# Macropad-Advanced.net
KiCad netlist of a schematic drawn in EasyEDA Pro
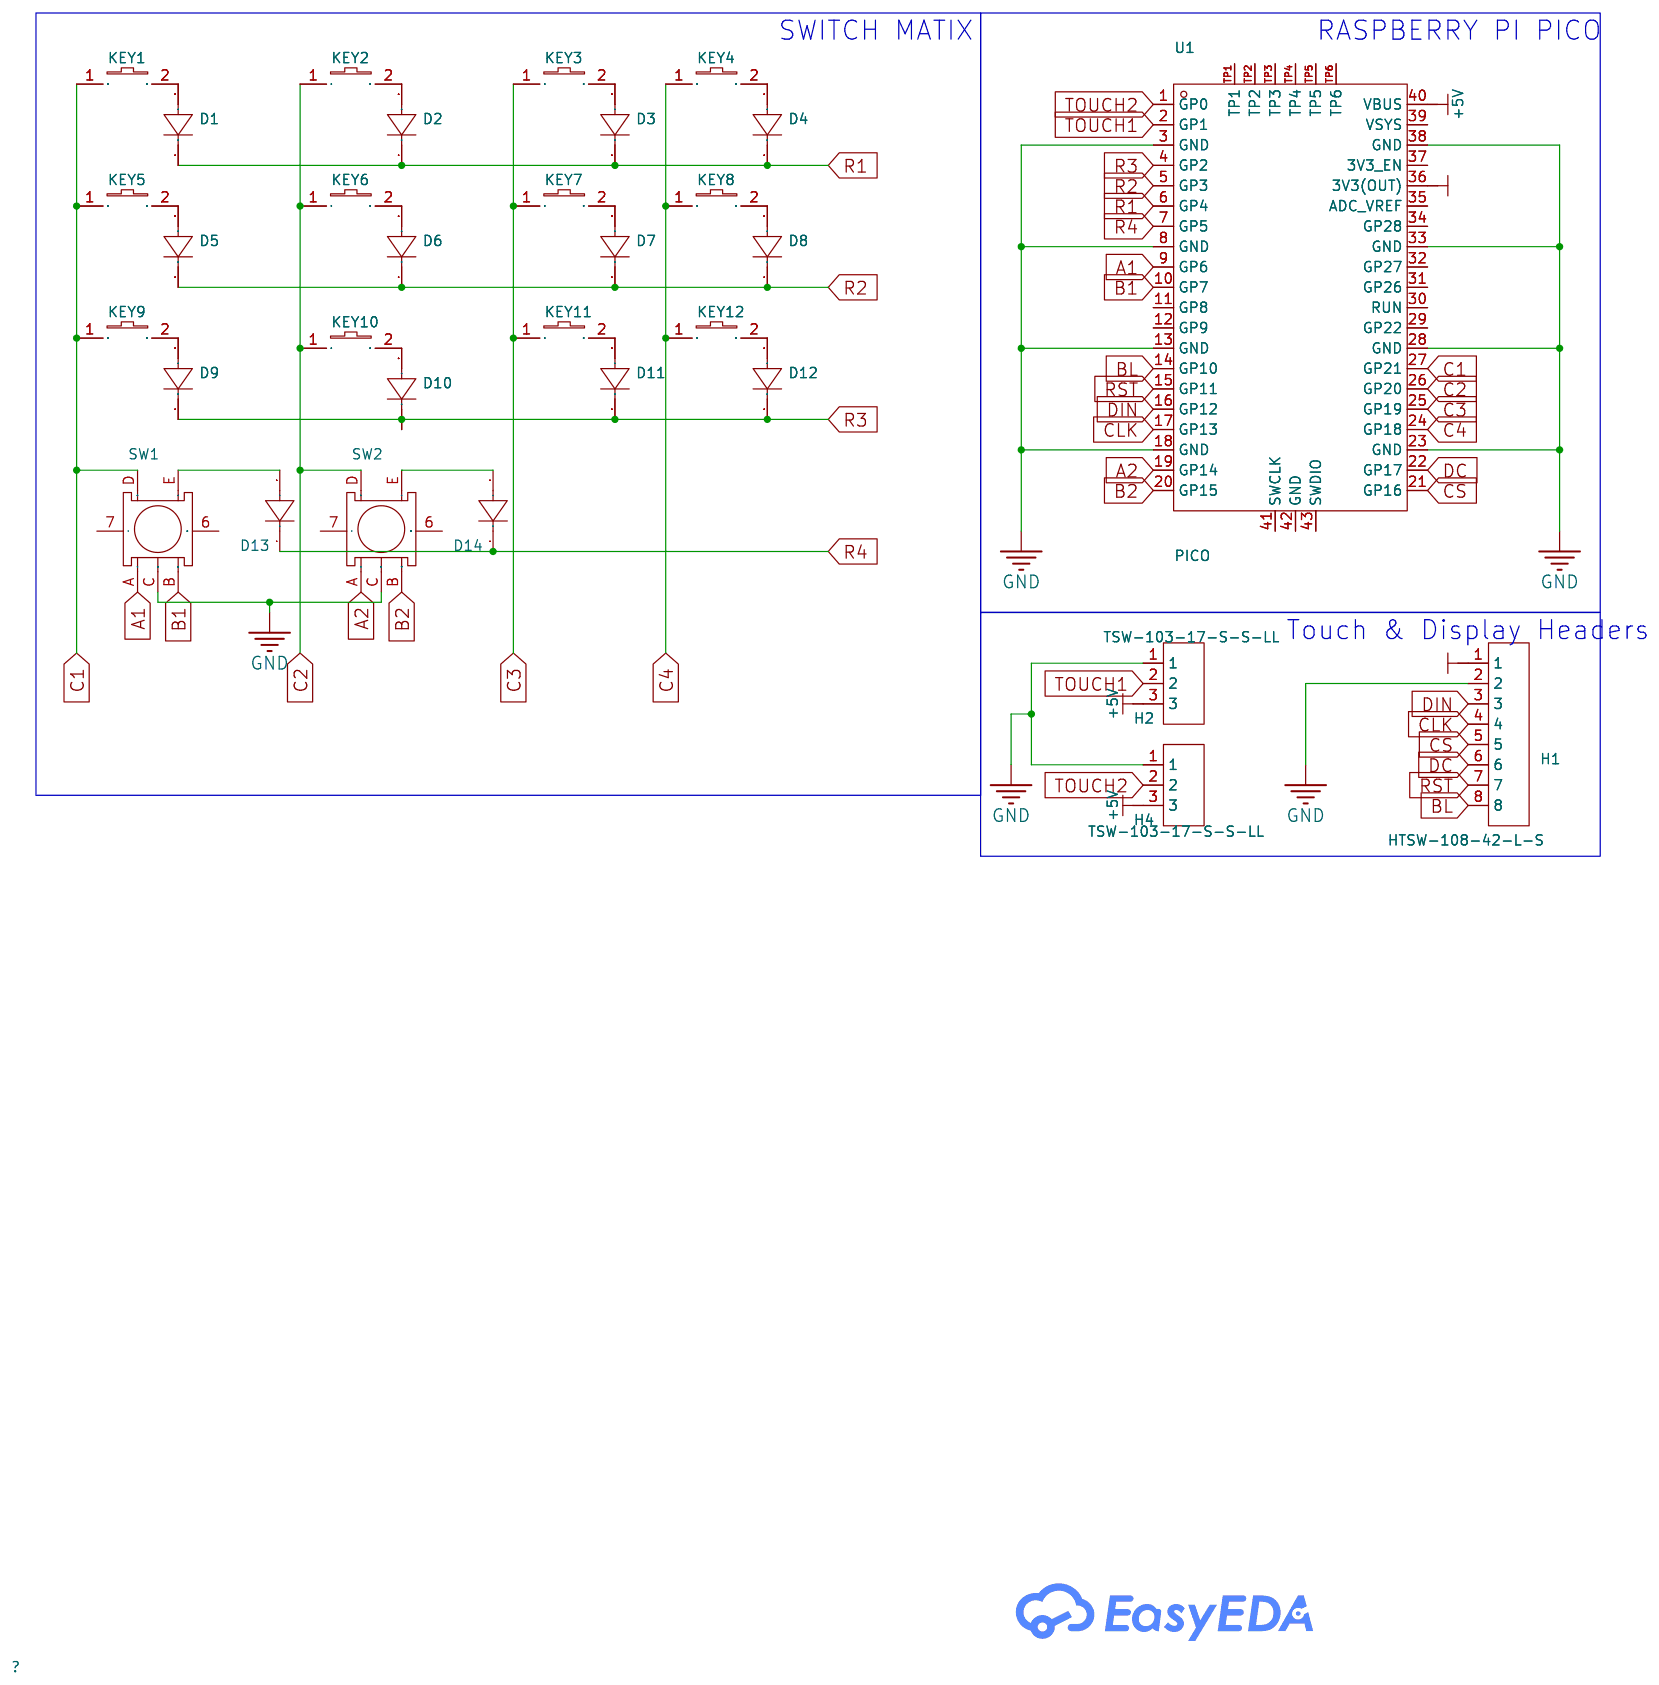
[diagram p0: schematic sheet]

(export (version "E")
  (design (tool "Eeschema 10.0.6"))
  (components
    (comp (ref "D1")
      (value "~")
      (footprint "easyedapro:DO-41_BD2.4-L4.7-P8.70-D0.9-RD")
      (fields (field (name "Manufacturer Part") "1N4148") (field (name "Manufacturer") "ST(先科)"))
      (libsource (lib "easyedapro") (part "D_1N4007"))
    )
    (comp (ref "D2")
      (value "~")
      (footprint "easyedapro:DO-41_BD2.4-L4.7-P8.70-D0.9-RD")
      (fields (field (name "Manufacturer Part") "1N4148") (field (name "Manufacturer") "ST(先科)"))
      (libsource (lib "easyedapro") (part "D_1N4007"))
    )
    (comp (ref "D3")
      (value "~")
      (footprint "easyedapro:DO-41_BD2.4-L4.7-P8.70-D0.9-RD")
      (fields (field (name "Manufacturer Part") "1N4148") (field (name "Manufacturer") "ST(先科)"))
      (libsource (lib "easyedapro") (part "D_1N4007"))
    )
    (comp (ref "D4")
      (value "~")
      (footprint "easyedapro:DO-41_BD2.4-L4.7-P8.70-D0.9-RD")
      (fields (field (name "Manufacturer Part") "1N4148") (field (name "Manufacturer") "ST(先科)"))
      (libsource (lib "easyedapro") (part "D_1N4007"))
    )
    (comp (ref "D5")
      (value "~")
      (footprint "easyedapro:DO-41_BD2.4-L4.7-P8.70-D0.9-RD")
      (fields (field (name "Manufacturer Part") "1N4148") (field (name "Manufacturer") "ST(先科)"))
      (libsource (lib "easyedapro") (part "D_1N4007"))
    )
    (comp (ref "D6")
      (value "~")
      (footprint "easyedapro:DO-41_BD2.4-L4.7-P8.70-D0.9-RD")
      (fields (field (name "Manufacturer Part") "1N4148") (field (name "Manufacturer") "ST(先科)"))
      (libsource (lib "easyedapro") (part "D_1N4007"))
    )
    (comp (ref "D7")
      (value "~")
      (footprint "easyedapro:DO-41_BD2.4-L4.7-P8.70-D0.9-RD")
      (fields (field (name "Manufacturer Part") "1N4148") (field (name "Manufacturer") "ST(先科)"))
      (libsource (lib "easyedapro") (part "D_1N4007"))
    )
    (comp (ref "D8")
      (value "~")
      (footprint "easyedapro:DO-41_BD2.4-L4.7-P8.70-D0.9-RD")
      (fields (field (name "Manufacturer Part") "1N4148") (field (name "Manufacturer") "ST(先科)"))
      (libsource (lib "easyedapro") (part "D_1N4007"))
    )
    (comp (ref "D9")
      (value "~")
      (footprint "easyedapro:DO-41_BD2.4-L4.7-P8.70-D0.9-RD")
      (fields (field (name "Manufacturer Part") "1N4148") (field (name "Manufacturer") "ST(先科)"))
      (libsource (lib "easyedapro") (part "D_1N4007"))
    )
    (comp (ref "D10")
      (value "~")
      (footprint "easyedapro:DO-41_BD2.4-L4.7-P8.70-D0.9-RD")
      (fields (field (name "Manufacturer Part") "1N4148") (field (name "Manufacturer") "ST(先科)"))
      (libsource (lib "easyedapro") (part "D_1N4007"))
    )
    (comp (ref "D11")
      (value "~")
      (footprint "easyedapro:DO-41_BD2.4-L4.7-P8.70-D0.9-RD")
      (fields (field (name "Manufacturer Part") "1N4148") (field (name "Manufacturer") "ST(先科)"))
      (libsource (lib "easyedapro") (part "D_1N4007"))
    )
    (comp (ref "D12")
      (value "~")
      (footprint "easyedapro:DO-41_BD2.4-L4.7-P8.70-D0.9-RD")
      (fields (field (name "Manufacturer Part") "1N4148") (field (name "Manufacturer") "ST(先科)"))
      (libsource (lib "easyedapro") (part "D_1N4007"))
    )
    (comp (ref "D13")
      (value "~")
      (footprint "easyedapro:DO-41_BD2.4-L4.7-P8.70-D0.9-RD")
      (fields (field (name "Manufacturer Part") "1N4148") (field (name "Manufacturer") "ST(先科)"))
      (libsource (lib "easyedapro") (part "D_1N4007"))
    )
    (comp (ref "D14")
      (value "~")
      (footprint "easyedapro:DO-41_BD2.4-L4.7-P8.70-D0.9-RD")
      (fields (field (name "Manufacturer Part") "1N4148") (field (name "Manufacturer") "ST(先科)"))
      (libsource (lib "easyedapro") (part "D_1N4007"))
    )
    (comp (ref "H1")
      (value "HTSW-108-42-L-S")
      (footprint "easyedapro:HDR-TH_8P-P2.54-V-M")
      (fields (field (name "Manufacturer") "SAMTEC"))
      (libsource (lib "easyedapro") (part "HTSW-108-42-L-S"))
    )
    (comp (ref "H2")
      (value "TSW-103-17-S-S-LL")
      (footprint "easyedapro:HDR-TH_3P-P2.54-V-M_HTSW-103-07-F-S")
      (fields (field (name "Manufacturer") "SAMTEC"))
      (libsource (lib "easyedapro") (part "TSW-103-17-S-S-LL"))
    )
    (comp (ref "H4")
      (value "TSW-103-17-S-S-LL")
      (footprint "easyedapro:HDR-TH_3P-P2.54-V-M_HTSW-103-07-F-S")
      (fields (field (name "Manufacturer") "SAMTEC"))
      (libsource (lib "easyedapro") (part "TSW-103-17-S-S-LL"))
    )
    (comp (ref "KEY1")
      (value "28115182DM")
      (footprint "easyedapro:MX_PCB_1.00u")
      (fields (field (name "Manufacturer") "SAMZO(三佐)"))
      (libsource (lib "easyedapro") (part "28115182DM"))
    )
    (comp (ref "KEY2")
      (value "28115182DM")
      (footprint "easyedapro:MX_PCB_1.00u")
      (fields (field (name "Manufacturer") "SAMZO(三佐)"))
      (libsource (lib "easyedapro") (part "28115182DM"))
    )
    (comp (ref "KEY3")
      (value "28115182DM")
      (footprint "easyedapro:MX_PCB_1.00u")
      (fields (field (name "Manufacturer") "SAMZO(三佐)"))
      (libsource (lib "easyedapro") (part "28115182DM"))
    )
    (comp (ref "KEY4")
      (value "28115182DM")
      (footprint "easyedapro:MX_PCB_1.00u")
      (fields (field (name "Manufacturer") "SAMZO(三佐)"))
      (libsource (lib "easyedapro") (part "28115182DM"))
    )
    (comp (ref "KEY5")
      (value "28115182DM")
      (footprint "easyedapro:MX_PCB_1.00u")
      (fields (field (name "Manufacturer") "SAMZO(三佐)"))
      (libsource (lib "easyedapro") (part "28115182DM"))
    )
    (comp (ref "KEY6")
      (value "28115182DM")
      (footprint "easyedapro:MX_PCB_1.00u")
      (fields (field (name "Manufacturer") "SAMZO(三佐)"))
      (libsource (lib "easyedapro") (part "28115182DM"))
    )
    (comp (ref "KEY7")
      (value "28115182DM")
      (footprint "easyedapro:MX_PCB_1.00u")
      (fields (field (name "Manufacturer") "SAMZO(三佐)"))
      (libsource (lib "easyedapro") (part "28115182DM"))
    )
    (comp (ref "KEY8")
      (value "28115182DM")
      (footprint "easyedapro:MX_PCB_1.00u")
      (fields (field (name "Manufacturer") "SAMZO(三佐)"))
      (libsource (lib "easyedapro") (part "28115182DM"))
    )
    (comp (ref "KEY9")
      (value "28115182DM")
      (footprint "easyedapro:MX_PCB_1.00u")
      (fields (field (name "Manufacturer") "SAMZO(三佐)"))
      (libsource (lib "easyedapro") (part "28115182DM"))
    )
    (comp (ref "KEY10")
      (value "28115182DM")
      (footprint "easyedapro:MX_PCB_1.00u")
      (fields (field (name "Manufacturer") "SAMZO(三佐)"))
      (libsource (lib "easyedapro") (part "28115182DM"))
    )
    (comp (ref "KEY11")
      (value "28115182DM")
      (footprint "easyedapro:MX_PCB_1.00u")
      (fields (field (name "Manufacturer") "SAMZO(三佐)"))
      (libsource (lib "easyedapro") (part "28115182DM"))
    )
    (comp (ref "KEY12")
      (value "28115182DM")
      (footprint "easyedapro:MX_PCB_1.00u")
      (fields (field (name "Manufacturer") "SAMZO(三佐)"))
      (libsource (lib "easyedapro") (part "28115182DM"))
    )
    (comp (ref "SW1")
      (value "EC11E09244BS")
      (footprint "easyedapro:SW-TH_EC11XXXXXXXX")
      (fields (field (name "Manufacturer") "ALPSALPINE(阿尔卑斯阿尔派)"))
      (libsource (lib "easyedapro") (part "EC11E09244BS"))
    )
    (comp (ref "SW2")
      (value "EC11E09244BS")
      (footprint "easyedapro:SW-TH_EC11XXXXXXXX")
      (fields (field (name "Manufacturer") "ALPSALPINE(阿尔卑斯阿尔派)"))
      (libsource (lib "easyedapro") (part "EC11E09244BS"))
    )
    (comp (ref "U1")
      (value "PICO")
      (footprint "easyedapro:Raspberry_Pi_Pico")
      (fields (field (name "Manufacturer") "Raspberry Pi(树莓派)"))
      (libsource (lib "easyedapro") (part "PICO"))
    )
  )
  (nets
    (net (code "1") (name "+5V") (class "Default")
      (node (ref "H2") (pin "3") (pinfunction "3_3") (pintype "unspecified"))
      (node (ref "H4") (pin "3") (pinfunction "3_3") (pintype "unspecified"))
      (node (ref "U1") (pin "40") (pinfunction "VBUS_40") (pintype "unspecified"))
    )
    (net (code "2") (name "3V3") (class "Default")
      (node (ref "H1") (pin "1") (pinfunction "1_1") (pintype "unspecified"))
      (node (ref "U1") (pin "36") (pinfunction "3V3(OUT)_36") (pintype "unspecified"))
    )
    (net (code "3") (name "A1") (class "Default")
      (node (ref "SW1") (pin "A") (pinfunction "A_A") (pintype "unspecified"))
      (node (ref "U1") (pin "9") (pinfunction "GP6_9") (pintype "unspecified"))
    )
    (net (code "4") (name "A2") (class "Default")
      (node (ref "SW2") (pin "A") (pinfunction "A_A") (pintype "unspecified"))
      (node (ref "U1") (pin "19") (pinfunction "GP14_19") (pintype "unspecified"))
    )
    (net (code "5") (name "B1") (class "Default")
      (node (ref "SW1") (pin "B") (pinfunction "B_B") (pintype "unspecified"))
      (node (ref "U1") (pin "10") (pinfunction "GP7_10") (pintype "unspecified"))
    )
    (net (code "6") (name "B2") (class "Default")
      (node (ref "SW2") (pin "B") (pinfunction "B_B") (pintype "unspecified"))
      (node (ref "U1") (pin "20") (pinfunction "GP15_20") (pintype "unspecified"))
    )
    (net (code "7") (name "BL") (class "Default")
      (node (ref "H1") (pin "8") (pinfunction "8_8") (pintype "unspecified"))
      (node (ref "U1") (pin "14") (pinfunction "GP10_14") (pintype "unspecified"))
    )
    (net (code "8") (name "C1") (class "Default")
      (node (ref "KEY1") (pin "1") (pinfunction "1_1") (pintype "unspecified"))
      (node (ref "KEY5") (pin "1") (pinfunction "1_1") (pintype "unspecified"))
      (node (ref "KEY9") (pin "1") (pinfunction "1_1") (pintype "unspecified"))
      (node (ref "SW1") (pin "D") (pinfunction "D_D") (pintype "unspecified"))
      (node (ref "U1") (pin "27") (pinfunction "GP21_27") (pintype "unspecified"))
    )
    (net (code "9") (name "C2") (class "Default")
      (node (ref "KEY10") (pin "1") (pinfunction "1_1") (pintype "unspecified"))
      (node (ref "KEY2") (pin "1") (pinfunction "1_1") (pintype "unspecified"))
      (node (ref "KEY6") (pin "1") (pinfunction "1_1") (pintype "unspecified"))
      (node (ref "SW2") (pin "D") (pinfunction "D_D") (pintype "unspecified"))
      (node (ref "U1") (pin "26") (pinfunction "GP20_26") (pintype "unspecified"))
    )
    (net (code "10") (name "C3") (class "Default")
      (node (ref "KEY11") (pin "1") (pinfunction "1_1") (pintype "unspecified"))
      (node (ref "KEY3") (pin "1") (pinfunction "1_1") (pintype "unspecified"))
      (node (ref "KEY7") (pin "1") (pinfunction "1_1") (pintype "unspecified"))
      (node (ref "U1") (pin "25") (pinfunction "GP19_25") (pintype "unspecified"))
    )
    (net (code "11") (name "C4") (class "Default")
      (node (ref "KEY12") (pin "1") (pinfunction "1_1") (pintype "unspecified"))
      (node (ref "KEY4") (pin "1") (pinfunction "1_1") (pintype "unspecified"))
      (node (ref "KEY8") (pin "1") (pinfunction "1_1") (pintype "unspecified"))
      (node (ref "U1") (pin "24") (pinfunction "GP18_24") (pintype "unspecified"))
    )
    (net (code "12") (name "CLK") (class "Default")
      (node (ref "H1") (pin "4") (pinfunction "4_4") (pintype "unspecified"))
      (node (ref "U1") (pin "17") (pinfunction "GP13_17") (pintype "unspecified"))
    )
    (net (code "13") (name "CS") (class "Default")
      (node (ref "H1") (pin "5") (pinfunction "5_5") (pintype "unspecified"))
      (node (ref "U1") (pin "21") (pinfunction "GP16_21") (pintype "unspecified"))
    )
    (net (code "14") (name "DC") (class "Default")
      (node (ref "H1") (pin "6") (pinfunction "6_6") (pintype "unspecified"))
      (node (ref "U1") (pin "22") (pinfunction "GP17_22") (pintype "unspecified"))
    )
    (net (code "15") (name "DIN") (class "Default")
      (node (ref "H1") (pin "3") (pinfunction "3_3") (pintype "unspecified"))
      (node (ref "U1") (pin "16") (pinfunction "GP12_16") (pintype "unspecified"))
    )
    (net (code "16") (name "GND") (class "Default")
      (node (ref "H1") (pin "2") (pinfunction "2_2") (pintype "unspecified"))
      (node (ref "H2") (pin "1") (pinfunction "1_1") (pintype "unspecified"))
      (node (ref "H4") (pin "1") (pinfunction "1_1") (pintype "unspecified"))
      (node (ref "SW1") (pin "C") (pinfunction "C_C") (pintype "unspecified"))
      (node (ref "SW2") (pin "C") (pinfunction "C_C") (pintype "unspecified"))
      (node (ref "U1") (pin "13") (pinfunction "GND_13") (pintype "unspecified"))
      (node (ref "U1") (pin "18") (pinfunction "GND_18") (pintype "unspecified"))
      (node (ref "U1") (pin "23") (pinfunction "GND_23") (pintype "unspecified"))
      (node (ref "U1") (pin "28") (pinfunction "GND_28") (pintype "unspecified"))
      (node (ref "U1") (pin "3") (pinfunction "GND_3") (pintype "unspecified"))
      (node (ref "U1") (pin "33") (pinfunction "GND_33") (pintype "unspecified"))
      (node (ref "U1") (pin "38") (pinfunction "GND_38") (pintype "unspecified"))
      (node (ref "U1") (pin "8") (pinfunction "GND_8") (pintype "unspecified"))
    )
    (net (code "17") (name "Net-(D1-A)") (class "Default")
      (node (ref "D1") (pin "2") (pinfunction "A_2") (pintype "input"))
      (node (ref "KEY1") (pin "2") (pinfunction "2_2") (pintype "unspecified"))
    )
    (net (code "18") (name "Net-(D2-A)") (class "Default")
      (node (ref "D2") (pin "2") (pinfunction "A_2") (pintype "input"))
      (node (ref "KEY2") (pin "2") (pinfunction "2_2") (pintype "unspecified"))
    )
    (net (code "19") (name "Net-(D3-A)") (class "Default")
      (node (ref "D3") (pin "2") (pinfunction "A_2") (pintype "input"))
      (node (ref "KEY3") (pin "2") (pinfunction "2_2") (pintype "unspecified"))
    )
    (net (code "20") (name "Net-(D4-A)") (class "Default")
      (node (ref "D4") (pin "2") (pinfunction "A_2") (pintype "input"))
      (node (ref "KEY4") (pin "2") (pinfunction "2_2") (pintype "unspecified"))
    )
    (net (code "21") (name "Net-(D5-A)") (class "Default")
      (node (ref "D5") (pin "2") (pinfunction "A_2") (pintype "input"))
      (node (ref "KEY5") (pin "2") (pinfunction "2_2") (pintype "unspecified"))
    )
    (net (code "22") (name "Net-(D6-A)") (class "Default")
      (node (ref "D6") (pin "2") (pinfunction "A_2") (pintype "input"))
      (node (ref "KEY6") (pin "2") (pinfunction "2_2") (pintype "unspecified"))
    )
    (net (code "23") (name "Net-(D7-A)") (class "Default")
      (node (ref "D7") (pin "2") (pinfunction "A_2") (pintype "input"))
      (node (ref "KEY7") (pin "2") (pinfunction "2_2") (pintype "unspecified"))
    )
    (net (code "24") (name "Net-(D8-A)") (class "Default")
      (node (ref "D8") (pin "2") (pinfunction "A_2") (pintype "input"))
      (node (ref "KEY8") (pin "2") (pinfunction "2_2") (pintype "unspecified"))
    )
    (net (code "25") (name "Net-(D9-A)") (class "Default")
      (node (ref "D9") (pin "2") (pinfunction "A_2") (pintype "input"))
      (node (ref "KEY9") (pin "2") (pinfunction "2_2") (pintype "unspecified"))
    )
    (net (code "26") (name "Net-(D10-A)") (class "Default")
      (node (ref "D10") (pin "2") (pinfunction "A_2") (pintype "input"))
      (node (ref "KEY10") (pin "2") (pinfunction "2_2") (pintype "unspecified"))
    )
    (net (code "27") (name "Net-(D11-A)") (class "Default")
      (node (ref "D11") (pin "2") (pinfunction "A_2") (pintype "input"))
      (node (ref "KEY11") (pin "2") (pinfunction "2_2") (pintype "unspecified"))
    )
    (net (code "28") (name "Net-(D12-A)") (class "Default")
      (node (ref "D12") (pin "2") (pinfunction "A_2") (pintype "input"))
      (node (ref "KEY12") (pin "2") (pinfunction "2_2") (pintype "unspecified"))
    )
    (net (code "29") (name "Net-(D13-A)") (class "Default")
      (node (ref "D13") (pin "2") (pinfunction "A_2") (pintype "input"))
      (node (ref "SW1") (pin "E") (pinfunction "E_E") (pintype "unspecified"))
    )
    (net (code "30") (name "Net-(D14-A)") (class "Default")
      (node (ref "D14") (pin "2") (pinfunction "A_2") (pintype "input"))
      (node (ref "SW2") (pin "E") (pinfunction "E_E") (pintype "unspecified"))
    )
    (net (code "31") (name "R1") (class "Default")
      (node (ref "D1") (pin "1") (pinfunction "K_1") (pintype "input"))
      (node (ref "D2") (pin "1") (pinfunction "K_1") (pintype "input"))
      (node (ref "D3") (pin "1") (pinfunction "K_1") (pintype "input"))
      (node (ref "D4") (pin "1") (pinfunction "K_1") (pintype "input"))
      (node (ref "U1") (pin "6") (pinfunction "GP4_6") (pintype "unspecified"))
    )
    (net (code "32") (name "R2") (class "Default")
      (node (ref "D5") (pin "1") (pinfunction "K_1") (pintype "input"))
      (node (ref "D6") (pin "1") (pinfunction "K_1") (pintype "input"))
      (node (ref "D7") (pin "1") (pinfunction "K_1") (pintype "input"))
      (node (ref "D8") (pin "1") (pinfunction "K_1") (pintype "input"))
      (node (ref "U1") (pin "5") (pinfunction "GP3_5") (pintype "unspecified"))
    )
    (net (code "33") (name "R3") (class "Default")
      (node (ref "D10") (pin "1") (pinfunction "K_1") (pintype "input"))
      (node (ref "D11") (pin "1") (pinfunction "K_1") (pintype "input"))
      (node (ref "D12") (pin "1") (pinfunction "K_1") (pintype "input"))
      (node (ref "D9") (pin "1") (pinfunction "K_1") (pintype "input"))
      (node (ref "U1") (pin "4") (pinfunction "GP2_4") (pintype "unspecified"))
    )
    (net (code "34") (name "R4") (class "Default")
      (node (ref "D13") (pin "1") (pinfunction "K_1") (pintype "input"))
      (node (ref "D14") (pin "1") (pinfunction "K_1") (pintype "input"))
      (node (ref "U1") (pin "7") (pinfunction "GP5_7") (pintype "unspecified"))
    )
    (net (code "35") (name "RST") (class "Default")
      (node (ref "H1") (pin "7") (pinfunction "7_7") (pintype "unspecified"))
      (node (ref "U1") (pin "15") (pinfunction "GP11_15") (pintype "unspecified"))
    )
    (net (code "36") (name "TOUCH1") (class "Default")
      (node (ref "H2") (pin "2") (pinfunction "2_2") (pintype "unspecified"))
      (node (ref "U1") (pin "2") (pinfunction "GP1_2") (pintype "unspecified"))
    )
    (net (code "37") (name "TOUCH2") (class "Default")
      (node (ref "H4") (pin "2") (pinfunction "2_2") (pintype "unspecified"))
      (node (ref "U1") (pin "1") (pinfunction "GP0_1") (pintype "unspecified"))
    )
    (net (code "38") (name "unconnected-(SW1-Pad6)") (class "Default")
      (node (ref "SW1") (pin "6") (pinfunction "6_6") (pintype "unspecified"))
    )
    (net (code "39") (name "unconnected-(SW1-Pad7)") (class "Default")
      (node (ref "SW1") (pin "7") (pinfunction "7_7") (pintype "unspecified"))
    )
    (net (code "40") (name "unconnected-(SW2-Pad6)") (class "Default")
      (node (ref "SW2") (pin "6") (pinfunction "6_6") (pintype "unspecified"))
    )
    (net (code "41") (name "unconnected-(SW2-Pad7)") (class "Default")
      (node (ref "SW2") (pin "7") (pinfunction "7_7") (pintype "unspecified"))
    )
    (net (code "42") (name "unconnected-(U1-3V3_EN-Pad37)") (class "Default")
      (node (ref "U1") (pin "37") (pinfunction "3V3_EN_37") (pintype "unspecified"))
    )
    (net (code "43") (name "unconnected-(U1-ADC_VREF-Pad35)") (class "Default")
      (node (ref "U1") (pin "35") (pinfunction "ADC_VREF_35") (pintype "unspecified"))
    )
    (net (code "44") (name "unconnected-(U1-GND-Pad42)") (class "Default")
      (node (ref "U1") (pin "42") (pinfunction "GND_42") (pintype "unspecified"))
    )
    (net (code "45") (name "unconnected-(U1-GP8-Pad11)") (class "Default")
      (node (ref "U1") (pin "11") (pinfunction "GP8_11") (pintype "unspecified"))
    )
    (net (code "46") (name "unconnected-(U1-GP9-Pad12)") (class "Default")
      (node (ref "U1") (pin "12") (pinfunction "GP9_12") (pintype "unspecified"))
    )
    (net (code "47") (name "unconnected-(U1-GP22-Pad29)") (class "Default")
      (node (ref "U1") (pin "29") (pinfunction "GP22_29") (pintype "unspecified"))
    )
    (net (code "48") (name "unconnected-(U1-GP26-Pad31)") (class "Default")
      (node (ref "U1") (pin "31") (pinfunction "GP26_31") (pintype "unspecified"))
    )
    (net (code "49") (name "unconnected-(U1-GP27-Pad32)") (class "Default")
      (node (ref "U1") (pin "32") (pinfunction "GP27_32") (pintype "unspecified"))
    )
    (net (code "50") (name "unconnected-(U1-GP28-Pad34)") (class "Default")
      (node (ref "U1") (pin "34") (pinfunction "GP28_34") (pintype "unspecified"))
    )
    (net (code "51") (name "unconnected-(U1-PadTP1)") (class "Default")
      (node (ref "U1") (pin "TP1") (pinfunction "TP1_TP1") (pintype "unspecified"))
    )
    (net (code "52") (name "unconnected-(U1-PadTP2)") (class "Default")
      (node (ref "U1") (pin "TP2") (pinfunction "TP2_TP2") (pintype "unspecified"))
    )
    (net (code "53") (name "unconnected-(U1-PadTP3)") (class "Default")
      (node (ref "U1") (pin "TP3") (pinfunction "TP3_TP3") (pintype "unspecified"))
    )
    (net (code "54") (name "unconnected-(U1-PadTP4)") (class "Default")
      (node (ref "U1") (pin "TP4") (pinfunction "TP4_TP4") (pintype "unspecified"))
    )
    (net (code "55") (name "unconnected-(U1-PadTP5)") (class "Default")
      (node (ref "U1") (pin "TP5") (pinfunction "TP5_TP5") (pintype "unspecified"))
    )
    (net (code "56") (name "unconnected-(U1-PadTP6)") (class "Default")
      (node (ref "U1") (pin "TP6") (pinfunction "TP6_TP6") (pintype "unspecified"))
    )
    (net (code "57") (name "unconnected-(U1-RUN-Pad30)") (class "Default")
      (node (ref "U1") (pin "30") (pinfunction "RUN_30") (pintype "unspecified"))
    )
    (net (code "58") (name "unconnected-(U1-SWCLK-Pad41)") (class "Default")
      (node (ref "U1") (pin "41") (pinfunction "SWCLK_41") (pintype "unspecified"))
    )
    (net (code "59") (name "unconnected-(U1-SWDIO-Pad43)") (class "Default")
      (node (ref "U1") (pin "43") (pinfunction "SWDIO_43") (pintype "unspecified"))
    )
    (net (code "60") (name "unconnected-(U1-VSYS-Pad39)") (class "Default")
      (node (ref "U1") (pin "39") (pinfunction "VSYS_39") (pintype "unspecified"))
    )
  )
)
